# Zio_Qwiic_SHT31_Temperature_Humidity_Sen.net
KiCad netlist of a schematic drawn in EAGLE
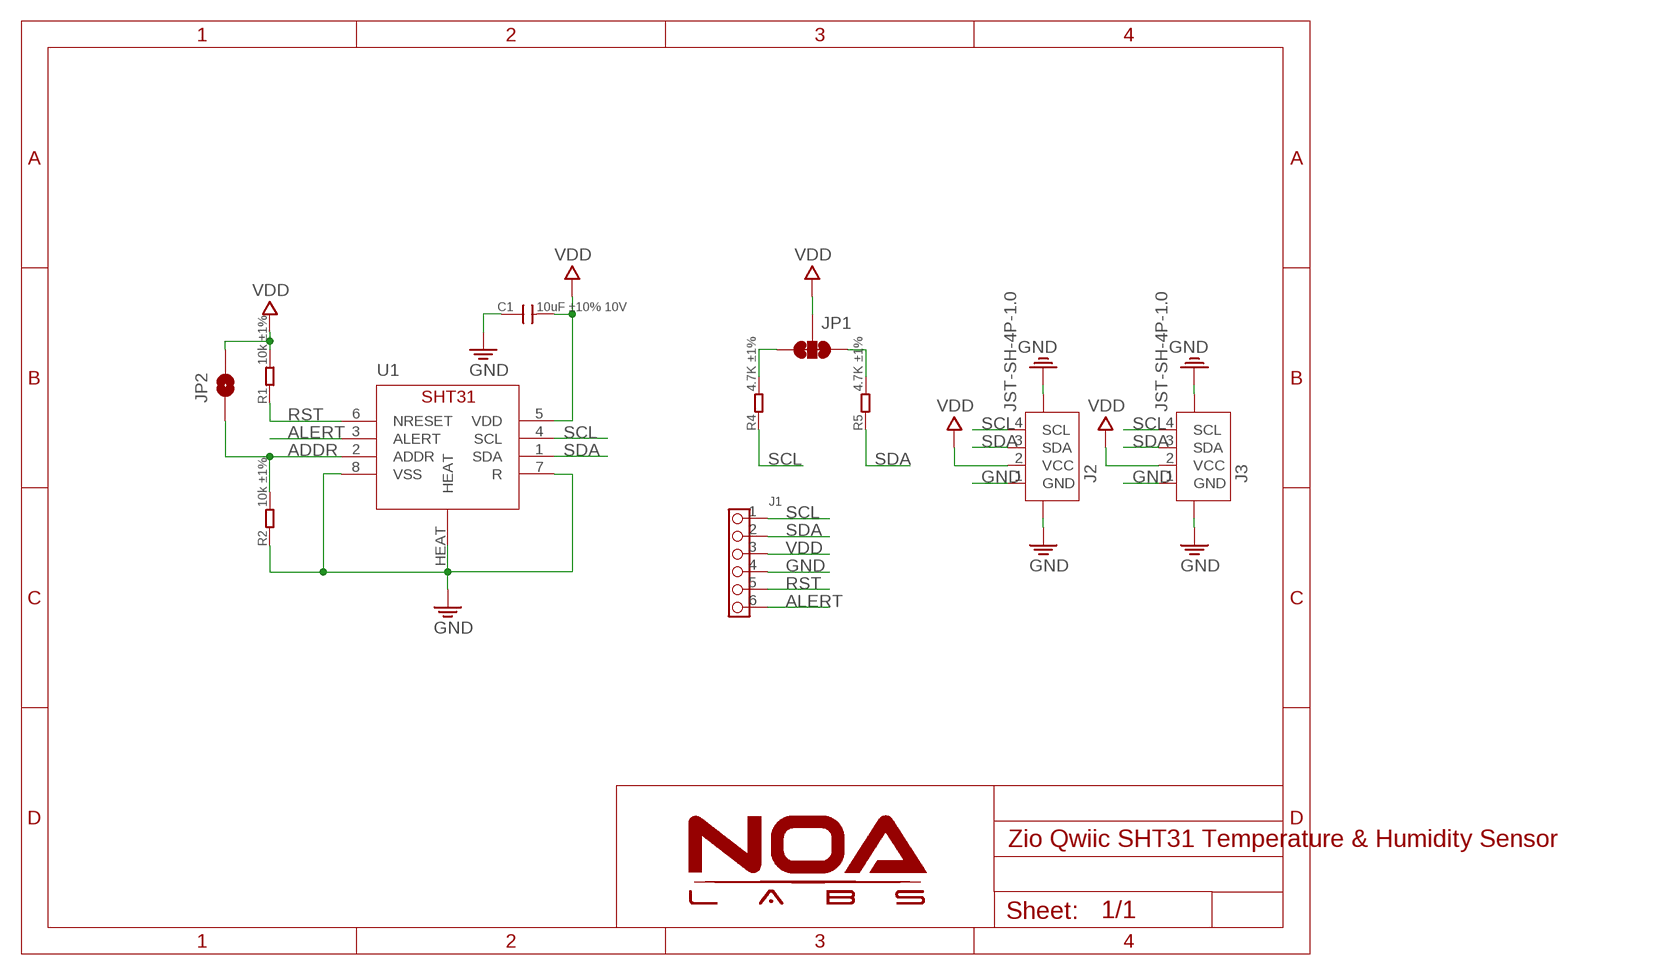
[diagram p0: schematic, sheet 1]

(export (version "E")
  (design (tool "Eeschema 10.0.6"))
  (components
    (comp (ref "C1")
      (value "10uF ±10% 10V")
      (footprint "eagle-import:C0603")
      (libsource (lib "eagle-import") (part "C-0603"))
    )
    (comp (ref "J1")
      (value "HEADER-6P-60/35MIL")
      (footprint "eagle-import:6P-2.54-60_35MIL")
      (libsource (lib "eagle-import") (part "HEADER-6P-60/35MIL"))
    )
    (comp (ref "J2")
      (value "JST-SH-4P-1.0")
      (footprint "eagle-import:JST-SH-4P")
      (libsource (lib "eagle-import") (part "JST-SH-4P-1.0"))
    )
    (comp (ref "J3")
      (value "JST-SH-4P-1.0")
      (footprint "eagle-import:JST-SH-4P")
      (libsource (lib "eagle-import") (part "JST-SH-4P-1.0"))
    )
    (comp (ref "JP1")
      (value "SMT-JUMPER_3_2-NC_TRACE")
      (footprint "eagle-import:SMT-JUMPER_3_2-NC_TRACE")
      (libsource (lib "eagle-import") (part "SMT-JUMPER_3_2-NC_TRACE"))
    )
    (comp (ref "JP2")
      (value "JUMPER-SMT_2_NC_PASTE_NOCREM")
      (footprint "eagle-import:SMT-JUMPER_2_NC_PASTE_SILK_NOCREM")
      (libsource (lib "eagle-import") (part "JUMPER-SMT_2_NC_PASTE_NOCREM"))
    )
    (comp (ref "R1")
      (value "10k ±1%")
      (footprint "eagle-import:R0603")
      (libsource (lib "eagle-import") (part "R-0603"))
    )
    (comp (ref "R2")
      (value "10k ±1%")
      (footprint "eagle-import:R0603")
      (libsource (lib "eagle-import") (part "R-0603"))
    )
    (comp (ref "R4")
      (value "4.7K ±1%")
      (footprint "eagle-import:R0603")
      (libsource (lib "eagle-import") (part "R-0603"))
    )
    (comp (ref "R5")
      (value "4.7K ±1%")
      (footprint "eagle-import:R0603")
      (libsource (lib "eagle-import") (part "R-0603"))
    )
    (comp (ref "U1")
      (value "SHT31")
      (footprint "eagle-import:DFN8")
      (libsource (lib "eagle-import") (part "SHT31"))
    )
  )
  (nets
    (net (code "1") (name "/ADDR") (class "Default")
      (node (ref "JP2") (pin "1") (pinfunction "1_1") (pintype "passive"))
      (node (ref "R2") (pin "2") (pinfunction "2_2") (pintype "passive"))
      (node (ref "U1") (pin "2") (pinfunction "ADDR_2") (pintype "bidirectional"))
    )
    (net (code "2") (name "/ALERT") (class "Default")
      (node (ref "J1") (pin "6") (pinfunction "6_6") (pintype "bidirectional"))
      (node (ref "U1") (pin "3") (pinfunction "ALERT_3") (pintype "bidirectional"))
    )
    (net (code "3") (name "/RST") (class "Default")
      (node (ref "J1") (pin "5") (pinfunction "5_5") (pintype "bidirectional"))
      (node (ref "R1") (pin "1") (pinfunction "1_1") (pintype "passive"))
      (node (ref "U1") (pin "6") (pinfunction "NRESET_6") (pintype "bidirectional"))
    )
    (net (code "4") (name "/SCL") (class "Default")
      (node (ref "J1") (pin "1") (pinfunction "1_1") (pintype "bidirectional"))
      (node (ref "J2") (pin "4") (pinfunction "SCL_4") (pintype "bidirectional"))
      (node (ref "J3") (pin "4") (pinfunction "SCL_4") (pintype "bidirectional"))
      (node (ref "R4") (pin "1") (pinfunction "1_1") (pintype "passive"))
      (node (ref "U1") (pin "4") (pinfunction "SCL_4") (pintype "bidirectional"))
    )
    (net (code "5") (name "/SDA") (class "Default")
      (node (ref "J1") (pin "2") (pinfunction "2_2") (pintype "bidirectional"))
      (node (ref "J2") (pin "3") (pinfunction "SDA_3") (pintype "bidirectional"))
      (node (ref "J3") (pin "3") (pinfunction "SDA_3") (pintype "bidirectional"))
      (node (ref "R5") (pin "1") (pinfunction "1_1") (pintype "passive"))
      (node (ref "U1") (pin "1") (pinfunction "SDA_1") (pintype "bidirectional"))
    )
    (net (code "6") (name "GND") (class "Default")
      (node (ref "C1") (pin "1") (pinfunction "1_1") (pintype "passive"))
      (node (ref "J1") (pin "4") (pinfunction "4_4") (pintype "bidirectional"))
      (node (ref "J2") (pin "1") (pinfunction "GND_1") (pintype "bidirectional"))
      (node (ref "J2") (pin "NC1") (pinfunction "5_NC1") (pintype "bidirectional"))
      (node (ref "J2") (pin "NC2") (pinfunction "6_NC2") (pintype "bidirectional"))
      (node (ref "J3") (pin "1") (pinfunction "GND_1") (pintype "bidirectional"))
      (node (ref "J3") (pin "NC1") (pinfunction "5_NC1") (pintype "bidirectional"))
      (node (ref "J3") (pin "NC2") (pinfunction "6_NC2") (pintype "bidirectional"))
      (node (ref "R2") (pin "1") (pinfunction "1_1") (pintype "passive"))
      (node (ref "U1") (pin "7") (pinfunction "R_7") (pintype "bidirectional"))
      (node (ref "U1") (pin "8") (pinfunction "VSS_8") (pintype "bidirectional"))
      (node (ref "U1") (pin "HEAT") (pinfunction "HEAT_HEAT") (pintype "bidirectional"))
    )
    (net (code "7") (name "Net-(JP1-Pad1)") (class "Default")
      (node (ref "JP1") (pin "1") (pinfunction "1_1") (pintype "passive"))
      (node (ref "R5") (pin "2") (pinfunction "2_2") (pintype "passive"))
    )
    (net (code "8") (name "Net-(JP1-Pad3)") (class "Default")
      (node (ref "JP1") (pin "3") (pinfunction "3_3") (pintype "passive"))
      (node (ref "R4") (pin "2") (pinfunction "2_2") (pintype "passive"))
    )
    (net (code "9") (name "VDD") (class "Default")
      (node (ref "C1") (pin "2") (pinfunction "2_2") (pintype "passive"))
      (node (ref "J1") (pin "3") (pinfunction "3_3") (pintype "bidirectional"))
      (node (ref "J2") (pin "2") (pinfunction "VCC_2") (pintype "bidirectional"))
      (node (ref "J3") (pin "2") (pinfunction "VCC_2") (pintype "bidirectional"))
      (node (ref "JP1") (pin "2") (pinfunction "2_2") (pintype "passive"))
      (node (ref "JP2") (pin "2") (pinfunction "2_2") (pintype "passive"))
      (node (ref "R1") (pin "2") (pinfunction "2_2") (pintype "passive"))
      (node (ref "U1") (pin "5") (pinfunction "VDD_5") (pintype "bidirectional"))
    )
  )
)
